# Transmitter.net
KiCad netlist of a schematic drawn in Altium Designer
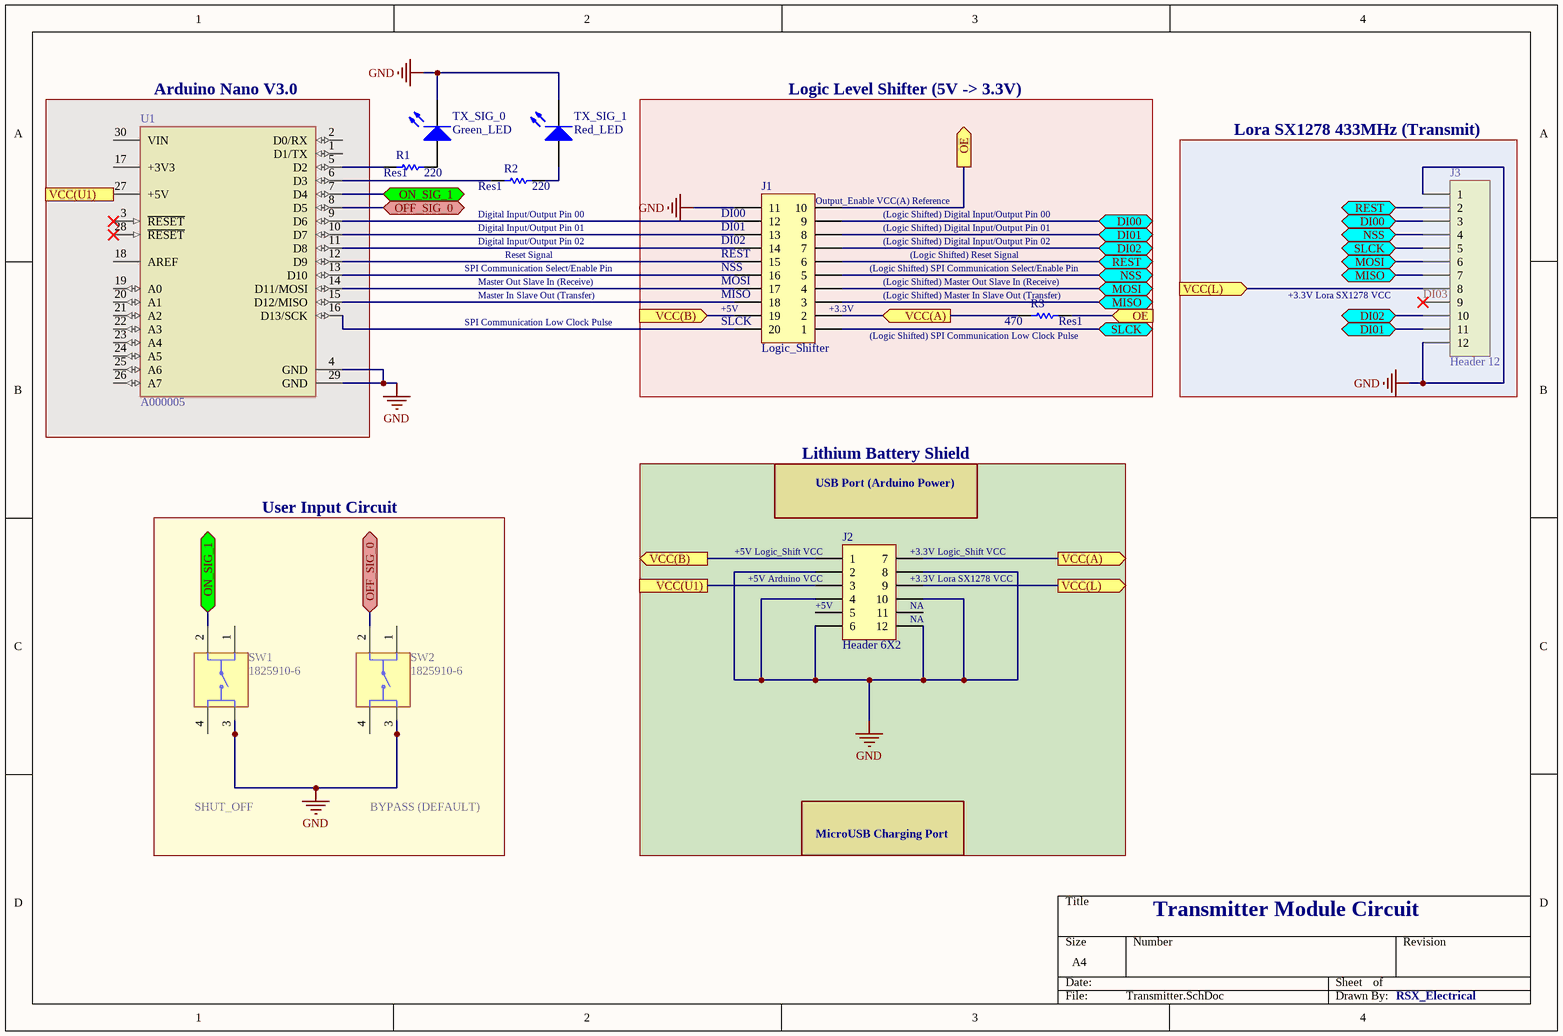
[diagram p0: Transmitter.SchDoc]

(export (version "E")
  (design (tool "Eeschema 10.0.6"))
  (components
    (comp (ref "J1")
      (value "Logic_Shifter")
      (footprint "DIP2SSOP20")
      (description "Header, 10-Pin, Dual row")
      (fields (field (name "PUBLISHER") "Altium Limited"))
      (libsource (lib "Miscellaneous Connectors") (part "Header 10X2"))
    )
    (comp (ref "J2")
      (value "Header 6X2")
      (footprint "HDR2X6")
      (description "Header, 6-Pin, Dual row")
      (fields (field (name "PUBLISHER") "Altium Limited"))
      (libsource (lib "Miscellaneous Connectors") (part "Header 6X2"))
    )
    (comp (ref "J3")
      (value "Header 12")
      (footprint "HDR1X12")
      (description "Header, 12-Pin")
      (fields (field (name "PUBLISHER") "Altium Limited"))
      (libsource (lib "Miscellaneous Connectors") (part "Header 12"))
    )
    (comp (ref "R1")
      (value "Res1")
      (footprint "AXIAL-0.3")
      (description "Resistor")
      (fields (field (name "ALTIUM_VALUE") "220") (field (name "PUBLISHER") "Altium Limited"))
      (libsource (lib "Miscellaneous Devices") (part "Res1"))
    )
    (comp (ref "R2")
      (value "Res1")
      (footprint "AXIAL-0.3")
      (description "Resistor")
      (fields (field (name "ALTIUM_VALUE") "220") (field (name "PUBLISHER") "Altium Limited"))
      (libsource (lib "Miscellaneous Devices") (part "Res1"))
    )
    (comp (ref "R3")
      (value "Res1")
      (footprint "AXIAL-0.3")
      (description "Resistor")
      (fields (field (name "ALTIUM_VALUE") "470") (field (name "PUBLISHER") "Altium Limited"))
      (libsource (lib "Miscellaneous Devices") (part "Res1"))
    )
    (comp (ref "SW1")
      (value "1825910-6")
      (footprint "SW_1825910-6-4")
      (description "Switch Tactile OFF (ON) SPST Round Button PC Pins 0.05A 24VDC 100000Cycles 1.57N Thru-Hole Loose")
      (libsource (lib "1825910-6") (part "1825910-6"))
    )
    (comp (ref "SW2")
      (value "1825910-6")
      (footprint "SW_1825910-6-4")
      (description "Switch Tactile OFF (ON) SPST Round Button PC Pins 0.05A 24VDC 100000Cycles 1.57N Thru-Hole Loose")
      (libsource (lib "1825910-6") (part "1825910-6"))
    )
    (comp (ref "TX_SIG_0")
      (value "Green_LED")
      (footprint "LED-0")
      (description "Typical INFRARED GaAs LED")
      (fields (field (name "PUBLISHER") "Altium Limited"))
      (libsource (lib "Miscellaneous Devices") (part "LED0"))
    )
    (comp (ref "TX_SIG_1")
      (value "Red_LED")
      (footprint "LED-0")
      (description "Typical INFRARED GaAs LED")
      (fields (field (name "PUBLISHER") "Altium Limited"))
      (libsource (lib "Miscellaneous Devices") (part "LED0"))
    )
    (comp (ref "U1")
      (value "A000005")
      (footprint "FP-A000005-MFG")
      (description "ARDUINO NANO ATMEGA328 EVAL BRD")
      (libsource (lib "Altium Content Vault") (part "d190c066e99afd1c6882cf92e11b2cc"))
    )
  )
  (nets
    (net (code "2") (name "/DI00") (class "Default")
      (node (ref "J1") (pin "9") (pinfunction "9_9") (pintype "passive"))
      (node (ref "J3") (pin "3") (pinfunction "3_3") (pintype "passive"))
    )
    (net (code "3") (name "/DI01") (class "Default")
      (node (ref "J1") (pin "8") (pinfunction "8_8") (pintype "passive"))
      (node (ref "J3") (pin "11") (pinfunction "11_11") (pintype "passive"))
    )
    (net (code "4") (name "/DI02") (class "Default")
      (node (ref "J1") (pin "7") (pinfunction "7_7") (pintype "passive"))
      (node (ref "J3") (pin "10") (pinfunction "10_10") (pintype "passive"))
    )
    (net (code "5") (name "/DI03") (class "Default")
      (node (ref "J3") (pin "9") (pinfunction "9_9") (pintype "passive+no_connect"))
    )
    (net (code "6") (name "/MISO") (class "Default")
      (node (ref "J1") (pin "3") (pinfunction "3_3") (pintype "passive"))
      (node (ref "J3") (pin "7") (pinfunction "7_7") (pintype "passive"))
    )
    (net (code "7") (name "/MOSI") (class "Default")
      (node (ref "J1") (pin "4") (pinfunction "4_4") (pintype "passive"))
      (node (ref "J3") (pin "6") (pinfunction "6_6") (pintype "passive"))
    )
    (net (code "8") (name "/NSS") (class "Default")
      (node (ref "J1") (pin "5") (pinfunction "5_5") (pintype "passive"))
      (node (ref "J3") (pin "4") (pinfunction "4_4") (pintype "passive"))
    )
    (net (code "9") (name "/OE") (class "Default")
      (node (ref "J1") (pin "10") (pinfunction "10_10") (pintype "passive"))
      (node (ref "R3") (pin "1") (pinfunction "1_1") (pintype "passive"))
    )
    (net (code "10") (name "/OFF_SIG_0") (class "Default")
      (node (ref "SW2") (pin "2") (pinfunction "2_2") (pintype "passive"))
      (node (ref "U1") (pin "8") (pinfunction "D5_8") (pintype "bidirectional"))
    )
    (net (code "11") (name "/ON_SIG_1") (class "Default")
      (node (ref "SW1") (pin "2") (pinfunction "2_2") (pintype "passive"))
      (node (ref "U1") (pin "7") (pinfunction "D4_7") (pintype "bidirectional"))
    )
    (net (code "12") (name "/REST") (class "Default")
      (node (ref "J1") (pin "6") (pinfunction "6_6") (pintype "passive"))
      (node (ref "J3") (pin "2") (pinfunction "2_2") (pintype "passive"))
    )
    (net (code "13") (name "/SLCK") (class "Default")
      (node (ref "J1") (pin "1") (pinfunction "1_1") (pintype "passive"))
      (node (ref "J3") (pin "5") (pinfunction "5_5") (pintype "passive"))
    )
    (net (code "14") (name "/VCC(A)") (class "Default")
      (node (ref "J1") (pin "2") (pinfunction "2_2") (pintype "passive"))
      (node (ref "J2") (pin "7") (pinfunction "7_7") (pintype "passive"))
      (node (ref "R3") (pin "2") (pinfunction "2_2") (pintype "passive"))
    )
    (net (code "15") (name "/VCC(B)") (class "Default")
      (node (ref "J1") (pin "19") (pinfunction "19_19") (pintype "passive"))
      (node (ref "J2") (pin "1") (pinfunction "1_1") (pintype "passive"))
    )
    (net (code "16") (name "/VCC(L)") (class "Default")
      (node (ref "J2") (pin "9") (pinfunction "9_9") (pintype "passive"))
      (node (ref "J3") (pin "8") (pinfunction "8_8") (pintype "passive"))
    )
    (net (code "17") (name "/VCC(U1)") (class "Default")
      (node (ref "J2") (pin "3") (pinfunction "3_3") (pintype "passive"))
      (node (ref "U1") (pin "27") (pinfunction "+5V_27") (pintype "power_in"))
    )
    (net (code "18") (name "GND") (class "Default")
      (node (ref "J1") (pin "11") (pinfunction "11_11") (pintype "passive"))
      (node (ref "J2") (pin "10") (pinfunction "10_10") (pintype "passive"))
      (node (ref "J2") (pin "12") (pinfunction "12_12") (pintype "passive"))
      (node (ref "J2") (pin "2") (pinfunction "2_2") (pintype "passive"))
      (node (ref "J2") (pin "4") (pinfunction "4_4") (pintype "passive"))
      (node (ref "J2") (pin "6") (pinfunction "6_6") (pintype "passive"))
      (node (ref "J2") (pin "8") (pinfunction "8_8") (pintype "passive"))
      (node (ref "J3") (pin "1") (pinfunction "1_1") (pintype "passive"))
      (node (ref "J3") (pin "12") (pinfunction "12_12") (pintype "passive"))
      (node (ref "SW1") (pin "3") (pinfunction "3_3") (pintype "passive"))
      (node (ref "SW2") (pin "3") (pinfunction "3_3") (pintype "passive"))
      (node (ref "TX_SIG_0") (pin "2") (pinfunction "K_2") (pintype "passive"))
      (node (ref "TX_SIG_1") (pin "2") (pinfunction "K_2") (pintype "passive"))
      (node (ref "U1") (pin "29") (pinfunction "GND_29") (pintype "power_in"))
      (node (ref "U1") (pin "4") (pinfunction "GND_4") (pintype "power_in"))
    )
    (net (code "19") (name "Net-(TX_SIG_0-A)") (class "Default")
      (node (ref "R1") (pin "1") (pinfunction "1_1") (pintype "passive"))
      (node (ref "TX_SIG_0") (pin "1") (pinfunction "A_1") (pintype "passive"))
    )
    (net (code "20") (name "Net-(TX_SIG_1-A)") (class "Default")
      (node (ref "R2") (pin "1") (pinfunction "1_1") (pintype "passive"))
      (node (ref "TX_SIG_1") (pin "1") (pinfunction "A_1") (pintype "passive"))
    )
    (net (code "21") (name "Net-(U1-D2)") (class "Default")
      (node (ref "R1") (pin "2") (pinfunction "2_2") (pintype "passive"))
      (node (ref "U1") (pin "5") (pinfunction "D2_5") (pintype "bidirectional"))
    )
    (net (code "22") (name "Net-(U1-D3)") (class "Default")
      (node (ref "R2") (pin "2") (pinfunction "2_2") (pintype "passive"))
      (node (ref "U1") (pin "6") (pinfunction "D3_6") (pintype "bidirectional"))
    )
    (net (code "23") (name "Net-(U1-D6)") (class "Default")
      (node (ref "J1") (pin "12") (pinfunction "12_12") (pintype "passive"))
      (node (ref "U1") (pin "9") (pinfunction "D6_9") (pintype "bidirectional"))
    )
    (net (code "24") (name "Net-(U1-D7)") (class "Default")
      (node (ref "J1") (pin "13") (pinfunction "13_13") (pintype "passive"))
      (node (ref "U1") (pin "10") (pinfunction "D7_10") (pintype "bidirectional"))
    )
    (net (code "25") (name "Net-(U1-D8)") (class "Default")
      (node (ref "J1") (pin "14") (pinfunction "14_14") (pintype "passive"))
      (node (ref "U1") (pin "11") (pinfunction "D8_11") (pintype "bidirectional"))
    )
    (net (code "26") (name "Net-(U1-D9)") (class "Default")
      (node (ref "J1") (pin "15") (pinfunction "15_15") (pintype "passive"))
      (node (ref "U1") (pin "12") (pinfunction "D9_12") (pintype "bidirectional"))
    )
    (net (code "27") (name "Net-(U1-D10)") (class "Default")
      (node (ref "J1") (pin "16") (pinfunction "16_16") (pintype "passive"))
      (node (ref "U1") (pin "13") (pinfunction "D10_13") (pintype "bidirectional"))
    )
    (net (code "28") (name "Net-(U1-D11{slash}MOSI)") (class "Default")
      (node (ref "J1") (pin "17") (pinfunction "17_17") (pintype "passive"))
      (node (ref "U1") (pin "14") (pinfunction "D11/MOSI_14") (pintype "bidirectional"))
    )
    (net (code "29") (name "Net-(U1-D12{slash}MISO)") (class "Default")
      (node (ref "J1") (pin "18") (pinfunction "18_18") (pintype "passive"))
      (node (ref "U1") (pin "15") (pinfunction "D12/MISO_15") (pintype "bidirectional"))
    )
    (net (code "30") (name "Net-(U1-D13{slash}SCK)") (class "Default")
      (node (ref "J1") (pin "20") (pinfunction "20_20") (pintype "passive"))
      (node (ref "U1") (pin "16") (pinfunction "D13/SCK_16") (pintype "bidirectional"))
    )
    (net (code "31") (name "unconnected-(J2-Pad5)") (class "Default")
      (node (ref "J2") (pin "5") (pinfunction "5_5") (pintype "passive"))
    )
    (net (code "32") (name "unconnected-(J2-Pad11)") (class "Default")
      (node (ref "J2") (pin "11") (pinfunction "11_11") (pintype "passive"))
    )
    (net (code "33") (name "unconnected-(SW1-Pad1)") (class "Default")
      (node (ref "SW1") (pin "1") (pinfunction "1_1") (pintype "passive"))
    )
    (net (code "34") (name "unconnected-(SW1-Pad4)") (class "Default")
      (node (ref "SW1") (pin "4") (pinfunction "4_4") (pintype "passive"))
    )
    (net (code "35") (name "unconnected-(SW2-Pad1)") (class "Default")
      (node (ref "SW2") (pin "1") (pinfunction "1_1") (pintype "passive"))
    )
    (net (code "36") (name "unconnected-(SW2-Pad4)") (class "Default")
      (node (ref "SW2") (pin "4") (pinfunction "4_4") (pintype "passive"))
    )
    (net (code "37") (name "unconnected-(U1-+3V3-Pad17)") (class "Default")
      (node (ref "U1") (pin "17") (pinfunction "+3V3_17") (pintype "power_in"))
    )
    (net (code "38") (name "unconnected-(U1-A0-Pad19)") (class "Default")
      (node (ref "U1") (pin "19") (pinfunction "A0_19") (pintype "bidirectional"))
    )
    (net (code "39") (name "unconnected-(U1-A1-Pad20)") (class "Default")
      (node (ref "U1") (pin "20") (pinfunction "A1_20") (pintype "bidirectional"))
    )
    (net (code "40") (name "unconnected-(U1-A2-Pad21)") (class "Default")
      (node (ref "U1") (pin "21") (pinfunction "A2_21") (pintype "bidirectional"))
    )
    (net (code "41") (name "unconnected-(U1-A3-Pad22)") (class "Default")
      (node (ref "U1") (pin "22") (pinfunction "A3_22") (pintype "bidirectional"))
    )
    (net (code "42") (name "unconnected-(U1-A4-Pad23)") (class "Default")
      (node (ref "U1") (pin "23") (pinfunction "A4_23") (pintype "bidirectional"))
    )
    (net (code "43") (name "unconnected-(U1-A5-Pad24)") (class "Default")
      (node (ref "U1") (pin "24") (pinfunction "A5_24") (pintype "bidirectional"))
    )
    (net (code "44") (name "unconnected-(U1-A6-Pad25)") (class "Default")
      (node (ref "U1") (pin "25") (pinfunction "A6_25") (pintype "bidirectional"))
    )
    (net (code "45") (name "unconnected-(U1-A7-Pad26)") (class "Default")
      (node (ref "U1") (pin "26") (pinfunction "A7_26") (pintype "bidirectional"))
    )
    (net (code "46") (name "unconnected-(U1-AREF-Pad18)") (class "Default")
      (node (ref "U1") (pin "18") (pinfunction "AREF_18") (pintype "passive"))
    )
    (net (code "47") (name "unconnected-(U1-D0{slash}RX-Pad2)") (class "Default")
      (node (ref "U1") (pin "2") (pinfunction "D0/RX_2") (pintype "bidirectional"))
    )
    (net (code "48") (name "unconnected-(U1-D1{slash}TX-Pad1)") (class "Default")
      (node (ref "U1") (pin "1") (pinfunction "D1/TX_1") (pintype "bidirectional"))
    )
    (net (code "49") (name "unconnected-(U1-VIN-Pad30)") (class "Default")
      (node (ref "U1") (pin "30") (pinfunction "VIN_30") (pintype "power_in"))
    )
    (net (code "50") (name "unconnected-(U1-~{RESET}-Pad3)") (class "Default")
      (node (ref "U1") (pin "3") (pinfunction "~{RESET}_3") (pintype "input+no_connect"))
    )
    (net (code "51") (name "unconnected-(U1-~{RESET}-Pad28)") (class "Default")
      (node (ref "U1") (pin "28") (pinfunction "~{RESET}_28") (pintype "input+no_connect"))
    )
  )
)
